# OZ440-SE140-CAR001_sheet4_Engagement_blo.net
KiCad netlist of a schematic drawn in Altium Designer
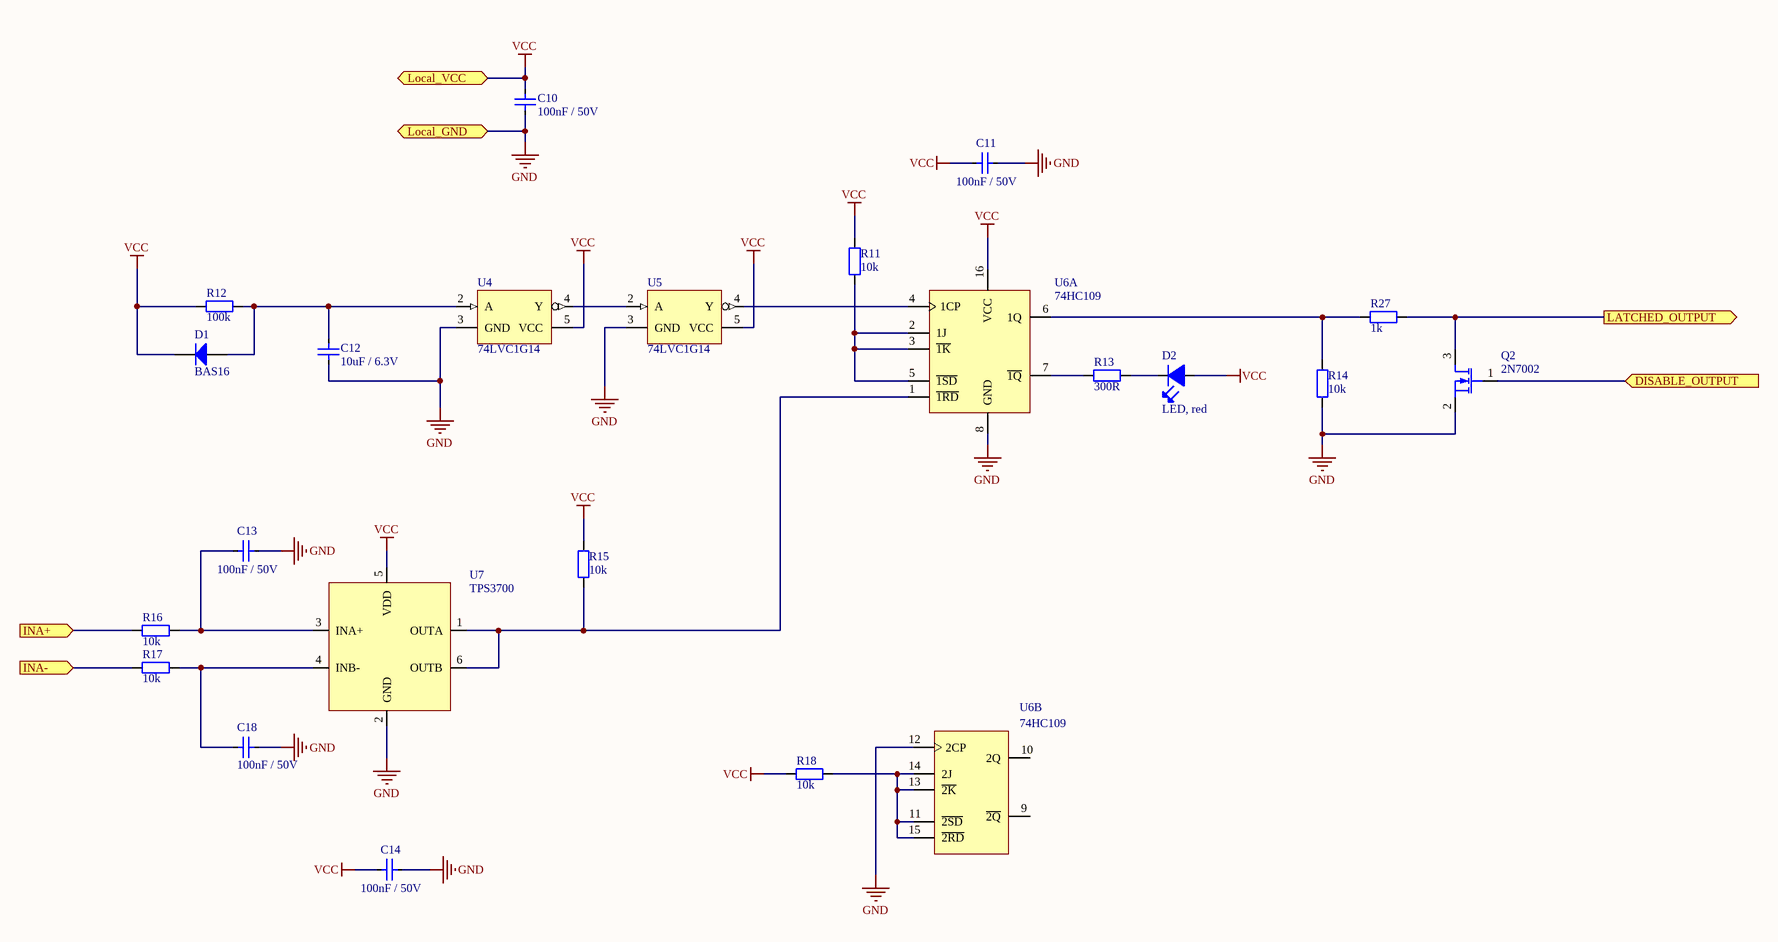
[diagram p0: OZ440-SE140-CAR001_sheet4_Engagement_block.SchDoc]

(export (version "E")
  (design (tool "Eeschema 10.0.6"))
  (components
    (comp (ref "C10")
      (value "CAP-SMD")
      (footprint "C0805-STD")
      (description "0805 100nF / 50V  X7R ceramic capacitor")
      (fields
        (field (name "DISPLAYED REFERENCE") "100nF / 50V")
        (field (name "TOLERANCE") "+/- 10%")
        (field (name "MANUFACTURER") "vishay")
      )
      (libsource (lib "lib_NAIO") (part "CAP-SMD"))
    )
    (comp (ref "C11")
      (value "CAP-SMD")
      (footprint "C0805-STD")
      (description "0805 100nF / 50V  X7R ceramic capacitor")
      (fields
        (field (name "DISPLAYED REFERENCE") "100nF / 50V")
        (field (name "TOLERANCE") "+/- 10%")
        (field (name "MANUFACTURER") "vishay")
      )
      (libsource (lib "lib_NAIO") (part "CAP-SMD"))
    )
    (comp (ref "C12")
      (value "CAP-SMD")
      (footprint "C0805-STD")
      (description "0805 10uF / 6.3V X5R ceramic capacitor")
      (fields
        (field (name "DISPLAYED REFERENCE") "10uF / 6.3V")
        (field (name "TOLERANCE") "+/- 10%")
        (field (name "MANUFACTURER") "Kemet")
      )
      (libsource (lib "lib_NAIO") (part "CAP-SMD"))
    )
    (comp (ref "C13")
      (value "CAP-SMD")
      (footprint "C0805-STD")
      (description "0805 100nF / 50V  X7R ceramic capacitor")
      (fields
        (field (name "DISPLAYED REFERENCE") "100nF / 50V")
        (field (name "TOLERANCE") "+/- 10%")
        (field (name "MANUFACTURER") "vishay")
      )
      (libsource (lib "lib_NAIO") (part "CAP-SMD"))
    )
    (comp (ref "C14")
      (value "CAP-SMD")
      (footprint "C0805-STD")
      (description "0805 100nF / 50V  X7R ceramic capacitor")
      (fields
        (field (name "DISPLAYED REFERENCE") "100nF / 50V")
        (field (name "TOLERANCE") "+/- 10%")
        (field (name "MANUFACTURER") "vishay")
      )
      (libsource (lib "lib_NAIO") (part "CAP-SMD"))
    )
    (comp (ref "C18")
      (value "CAP-SMD")
      (footprint "C0805-STD")
      (description "0805 100nF / 50V  X7R ceramic capacitor")
      (fields
        (field (name "DISPLAYED REFERENCE") "100nF / 50V")
        (field (name "TOLERANCE") "+/- 10%")
        (field (name "MANUFACTURER") "vishay")
      )
      (libsource (lib "lib_NAIO") (part "CAP-SMD"))
    )
    (comp (ref "D1")
      (value "BAS16-SOT23")
      (footprint "SOT23-STD")
      (description "100V / 120mA signal  diode")
      (fields (field (name "DISPLAYED REFERENCE") "BAS16") (field (name "MANUFACTURER") "NXP"))
      (libsource (lib "lib_NAIO") (part "BAS16-SOT23"))
    )
    (comp (ref "D2")
      (value "LED")
      (footprint "LED_3MM")
      (description "LED 3mm red TH")
      (fields (field (name "DISPLAYED REFERENCE") "LED, red") (field (name "MANUFACTURER") "MULTICOMP"))
      (libsource (lib "lib_NAIO") (part "LED"))
    )
    (comp (ref "Q2")
      (value "2N7002-SMD3P")
      (footprint "SOT23-SPE-2N7002")
      (description "N-Channel Enhancement Mode Field Effect Transistor")
      (fields (field (name "DISPLAYED REFERENCE") "2N7002") (field (name "MANUFACTURER") "FAIRCHILD"))
      (libsource (lib "lib_NAIO") (part "2N7002-SMD3P"))
    )
    (comp (ref "R11")
      (value "RES-SMD")
      (footprint "R0805-STD")
      (description "10k Ohm 0805 SMD resistor")
      (fields
        (field (name "DISPLAYED REFERENCE") "10k")
        (field (name "TOLERANCE") "1 %")
        (field (name "MANUFACTURER") "Vishay")
      )
      (libsource (lib "") (part "RES-SMD_1"))
    )
    (comp (ref "R12")
      (value "RES-SMD")
      (footprint "R0805-STD")
      (description "100k Ohm 0805 SMD resistor")
      (fields
        (field (name "DISPLAYED REFERENCE") "100k")
        (field (name "TOLERANCE") "1 %")
        (field (name "MANUFACTURER") "Vishay")
      )
      (libsource (lib "lib_NAIO") (part "RES-SMD"))
    )
    (comp (ref "R13")
      (value "RES-SMD")
      (footprint "R0805-STD")
      (description "300 ohm 0805 SMD resistor")
      (fields
        (field (name "DISPLAYED REFERENCE") "300R")
        (field (name "TOLERANCE") "1%")
        (field (name "MANUFACTURER") "Vishay")
      )
      (libsource (lib "lib_NAIO") (part "RES-SMD"))
    )
    (comp (ref "R14")
      (value "RES-SMD")
      (footprint "R0805-STD")
      (description "10k Ohm 0805 SMD resistor")
      (fields
        (field (name "DISPLAYED REFERENCE") "10k")
        (field (name "TOLERANCE") "1 %")
        (field (name "MANUFACTURER") "Vishay")
      )
      (libsource (lib "") (part "RES-SMD_1"))
    )
    (comp (ref "R15")
      (value "RES-SMD")
      (footprint "R0805-STD")
      (description "10k Ohm 0805 SMD resistor")
      (fields
        (field (name "DISPLAYED REFERENCE") "10k")
        (field (name "TOLERANCE") "1 %")
        (field (name "MANUFACTURER") "Vishay")
      )
      (libsource (lib "") (part "RES-SMD_1"))
    )
    (comp (ref "R16")
      (value "RES-SMD")
      (footprint "R0805-STD")
      (description "10k Ohm 0805 SMD resistor")
      (fields
        (field (name "DISPLAYED REFERENCE") "10k")
        (field (name "TOLERANCE") "1 %")
        (field (name "MANUFACTURER") "Vishay")
      )
      (libsource (lib "lib_NAIO") (part "RES-SMD"))
    )
    (comp (ref "R17")
      (value "RES-SMD")
      (footprint "R0805-STD")
      (description "10k Ohm 0805 SMD resistor")
      (fields
        (field (name "DISPLAYED REFERENCE") "10k")
        (field (name "TOLERANCE") "1 %")
        (field (name "MANUFACTURER") "Vishay")
      )
      (libsource (lib "lib_NAIO") (part "RES-SMD"))
    )
    (comp (ref "R18")
      (value "RES-SMD")
      (footprint "R0805-STD")
      (description "10k Ohm 0805 SMD resistor")
      (fields
        (field (name "DISPLAYED REFERENCE") "10k")
        (field (name "TOLERANCE") "1 %")
        (field (name "MANUFACTURER") "Vishay")
      )
      (libsource (lib "lib_NAIO") (part "RES-SMD"))
    )
    (comp (ref "R27")
      (value "RES-SMD")
      (footprint "R0805-STD")
      (description "1k Ohm 0805 SMD resistor")
      (fields
        (field (name "DISPLAYED REFERENCE") "1k")
        (field (name "TOLERANCE") "1 %")
        (field (name "MANUFACTURER") "Vishay")
      )
      (libsource (lib "") (part "RES-SMD_2"))
    )
    (comp (ref "U4")
      (value "74xxx1G14GW-SOT353-1")
      (footprint "SOT353-1_5pin-STD")
      (description "smith trigger inverter")
      (fields (field (name "DISPLAYED REFERENCE") "74LVC1G14") (field (name "MANUFACTURER") "NXP"))
      (libsource (lib "lib_NAIO") (part "74xxx1G14GW-SOT353-1"))
    )
    (comp (ref "U5")
      (value "74xxx1G14GW-SOT353-1")
      (footprint "SOT353-1_5pin-STD")
      (description "smith trigger inverter")
      (fields (field (name "DISPLAYED REFERENCE") "74LVC1G14") (field (name "MANUFACTURER") "NXP"))
      (libsource (lib "lib_NAIO") (part "74xxx1G14GW-SOT353-1"))
    )
    (comp (ref "U6")
      (value "74xxx109DB-TSSOP16")
      (footprint "TSSOP16-SPE-74HC109")
      (description "Dual JK flip-flop with set and reset")
      (fields (field (name "DISPLAYED REFERENCE") "74HC109") (field (name "MANUFACTURER") "NXP"))
      (libsource (lib "lib_NAIO") (part "74xxx109DB-TSSOP16"))
    )
    (comp (ref "U7")
      (value "TPS3700-SOT23-6")
      (footprint "SOT23_6-SPE-TPS3700")
      (description "Window Comparator for Over- and Undervoltage Detection")
      (fields (field (name "DISPLAYED REFERENCE") "TPS3700") (field (name "MANUFACTURER") "TI"))
      (libsource (lib "lib_NAIO") (part "TPS3700-SOT23-6"))
    )
  )
  (nets
    (net (code "1") (name "/DISABLE_OUTPUT") (class "Default")
      (node (ref "Q2") (pin "1") (pinfunction "G_1") (pintype "passive"))
    )
    (net (code "2") (name "/INA+") (class "Default")
      (node (ref "R16") (pin "1") (pinfunction "1_1") (pintype "passive"))
    )
    (net (code "3") (name "/INA-") (class "Default")
      (node (ref "R17") (pin "1") (pinfunction "1_1") (pintype "passive"))
    )
    (net (code "4") (name "/LATCHED_OUTPUT") (class "Default")
      (node (ref "Q2") (pin "3") (pinfunction "D_3") (pintype "passive"))
      (node (ref "R27") (pin "1") (pinfunction "1_1") (pintype "passive"))
    )
    (net (code "5") (name "GND") (class "Default")
      (node (ref "C10") (pin "2") (pinfunction "2_2") (pintype "passive"))
      (node (ref "C11") (pin "2") (pinfunction "2_2") (pintype "passive"))
      (node (ref "C12") (pin "1") (pinfunction "1_1") (pintype "passive"))
      (node (ref "C13") (pin "2") (pinfunction "2_2") (pintype "passive"))
      (node (ref "C14") (pin "2") (pinfunction "2_2") (pintype "passive"))
      (node (ref "C18") (pin "2") (pinfunction "2_2") (pintype "passive"))
      (node (ref "Q2") (pin "2") (pinfunction "S_2") (pintype "passive"))
      (node (ref "R14") (pin "2") (pinfunction "2_2") (pintype "passive"))
      (node (ref "U4") (pin "3") (pinfunction "GND_3") (pintype "power_in"))
      (node (ref "U5") (pin "3") (pinfunction "GND_3") (pintype "power_in"))
      (node (ref "U6") (pin "12") (pinfunction "2CP_12") (pintype "passive"))
      (node (ref "U6") (pin "8") (pinfunction "GND_8") (pintype "passive"))
      (node (ref "U7") (pin "2") (pinfunction "GND_2") (pintype "passive"))
    )
    (net (code "6") (name "Net-(D1-A)") (class "Default")
      (node (ref "C12") (pin "2") (pinfunction "2_2") (pintype "passive"))
      (node (ref "D1") (pin "1") (pinfunction "A_1") (pintype "passive"))
      (node (ref "R12") (pin "2") (pinfunction "2_2") (pintype "passive"))
      (node (ref "U4") (pin "2") (pinfunction "A_2") (pintype "input"))
    )
    (net (code "7") (name "Net-(D2-Pad2)") (class "Default")
      (node (ref "D2") (pin "2") (pinfunction "2_2") (pintype "passive"))
      (node (ref "R13") (pin "2") (pinfunction "2_2") (pintype "passive"))
    )
    (net (code "8") (name "Net-(R13-Pad1)") (class "Default")
      (node (ref "R13") (pin "1") (pinfunction "1_1") (pintype "passive"))
      (node (ref "U6") (pin "7") (pinfunction "1Q_7") (pintype "passive"))
    )
    (net (code "9") (name "Net-(R14-Pad1)") (class "Default")
      (node (ref "R14") (pin "1") (pinfunction "1_1") (pintype "passive"))
      (node (ref "R27") (pin "2") (pinfunction "2_2") (pintype "passive"))
      (node (ref "U6") (pin "6") (pinfunction "1Q_6") (pintype "passive"))
    )
    (net (code "10") (name "Net-(U4-Y)") (class "Default")
      (node (ref "U4") (pin "4") (pinfunction "Y_4") (pintype "output"))
      (node (ref "U5") (pin "2") (pinfunction "A_2") (pintype "input"))
    )
    (net (code "11") (name "Net-(U5-Y)") (class "Default")
      (node (ref "U5") (pin "4") (pinfunction "Y_4") (pintype "output"))
      (node (ref "U6") (pin "4") (pinfunction "1CP_4") (pintype "passive"))
    )
    (net (code "12") (name "Net-(U6A-1J)") (class "Default")
      (node (ref "R11") (pin "2") (pinfunction "2_2") (pintype "passive"))
      (node (ref "U6") (pin "2") (pinfunction "1J_2") (pintype "passive"))
      (node (ref "U6") (pin "3") (pinfunction "1K_3") (pintype "power_in"))
      (node (ref "U6") (pin "5") (pinfunction "1SD_5") (pintype "power_in"))
    )
    (net (code "13") (name "Net-(U6A-1RD)") (class "Default")
      (node (ref "R15") (pin "2") (pinfunction "2_2") (pintype "passive"))
      (node (ref "U6") (pin "1") (pinfunction "1RD_1") (pintype "power_in"))
      (node (ref "U7") (pin "1") (pinfunction "OUTA_1") (pintype "passive"))
      (node (ref "U7") (pin "6") (pinfunction "OUTB_6") (pintype "passive"))
    )
    (net (code "14") (name "Net-(U6B-2J)") (class "Default")
      (node (ref "R18") (pin "2") (pinfunction "2_2") (pintype "passive"))
      (node (ref "U6") (pin "11") (pinfunction "2SD_11") (pintype "power_in"))
      (node (ref "U6") (pin "13") (pinfunction "2K_13") (pintype "power_in"))
      (node (ref "U6") (pin "14") (pinfunction "2J_14") (pintype "passive"))
      (node (ref "U6") (pin "15") (pinfunction "2RD_15") (pintype "power_in"))
    )
    (net (code "15") (name "Net-(U7-INA+)") (class "Default")
      (node (ref "C13") (pin "1") (pinfunction "1_1") (pintype "passive"))
      (node (ref "R16") (pin "2") (pinfunction "2_2") (pintype "passive"))
      (node (ref "U7") (pin "3") (pinfunction "INA+_3") (pintype "passive"))
    )
    (net (code "16") (name "Net-(U7-INB-)") (class "Default")
      (node (ref "C18") (pin "1") (pinfunction "1_1") (pintype "passive"))
      (node (ref "R17") (pin "2") (pinfunction "2_2") (pintype "passive"))
      (node (ref "U7") (pin "4") (pinfunction "INB-_4") (pintype "passive"))
    )
    (net (code "17") (name "VCC") (class "Default")
      (node (ref "C10") (pin "1") (pinfunction "1_1") (pintype "passive"))
      (node (ref "C11") (pin "1") (pinfunction "1_1") (pintype "passive"))
      (node (ref "C14") (pin "1") (pinfunction "1_1") (pintype "passive"))
      (node (ref "D1") (pin "3") (pinfunction "K_3") (pintype "passive"))
      (node (ref "D2") (pin "1") (pinfunction "A_1") (pintype "passive"))
      (node (ref "R11") (pin "1") (pinfunction "1_1") (pintype "passive"))
      (node (ref "R12") (pin "1") (pinfunction "1_1") (pintype "passive"))
      (node (ref "R15") (pin "1") (pinfunction "1_1") (pintype "passive"))
      (node (ref "R18") (pin "1") (pinfunction "1_1") (pintype "passive"))
      (node (ref "U4") (pin "5") (pinfunction "VCC_5") (pintype "power_in"))
      (node (ref "U5") (pin "5") (pinfunction "VCC_5") (pintype "power_in"))
      (node (ref "U6") (pin "16") (pinfunction "VCC_16") (pintype "passive"))
      (node (ref "U7") (pin "5") (pinfunction "VDD_5") (pintype "passive"))
    )
    (net (code "18") (name "unconnected-(U6B-2Q-Pad9)") (class "Default")
      (node (ref "U6") (pin "9") (pinfunction "2Q_9") (pintype "passive"))
    )
    (net (code "19") (name "unconnected-(U6B-2Q-Pad10)") (class "Default")
      (node (ref "U6") (pin "10") (pinfunction "2Q_10") (pintype "passive"))
    )
  )
)
